# ProProject_MinSyBo_Star_2024-05-27.net
KiCad netlist of a schematic drawn in EasyEDA Pro
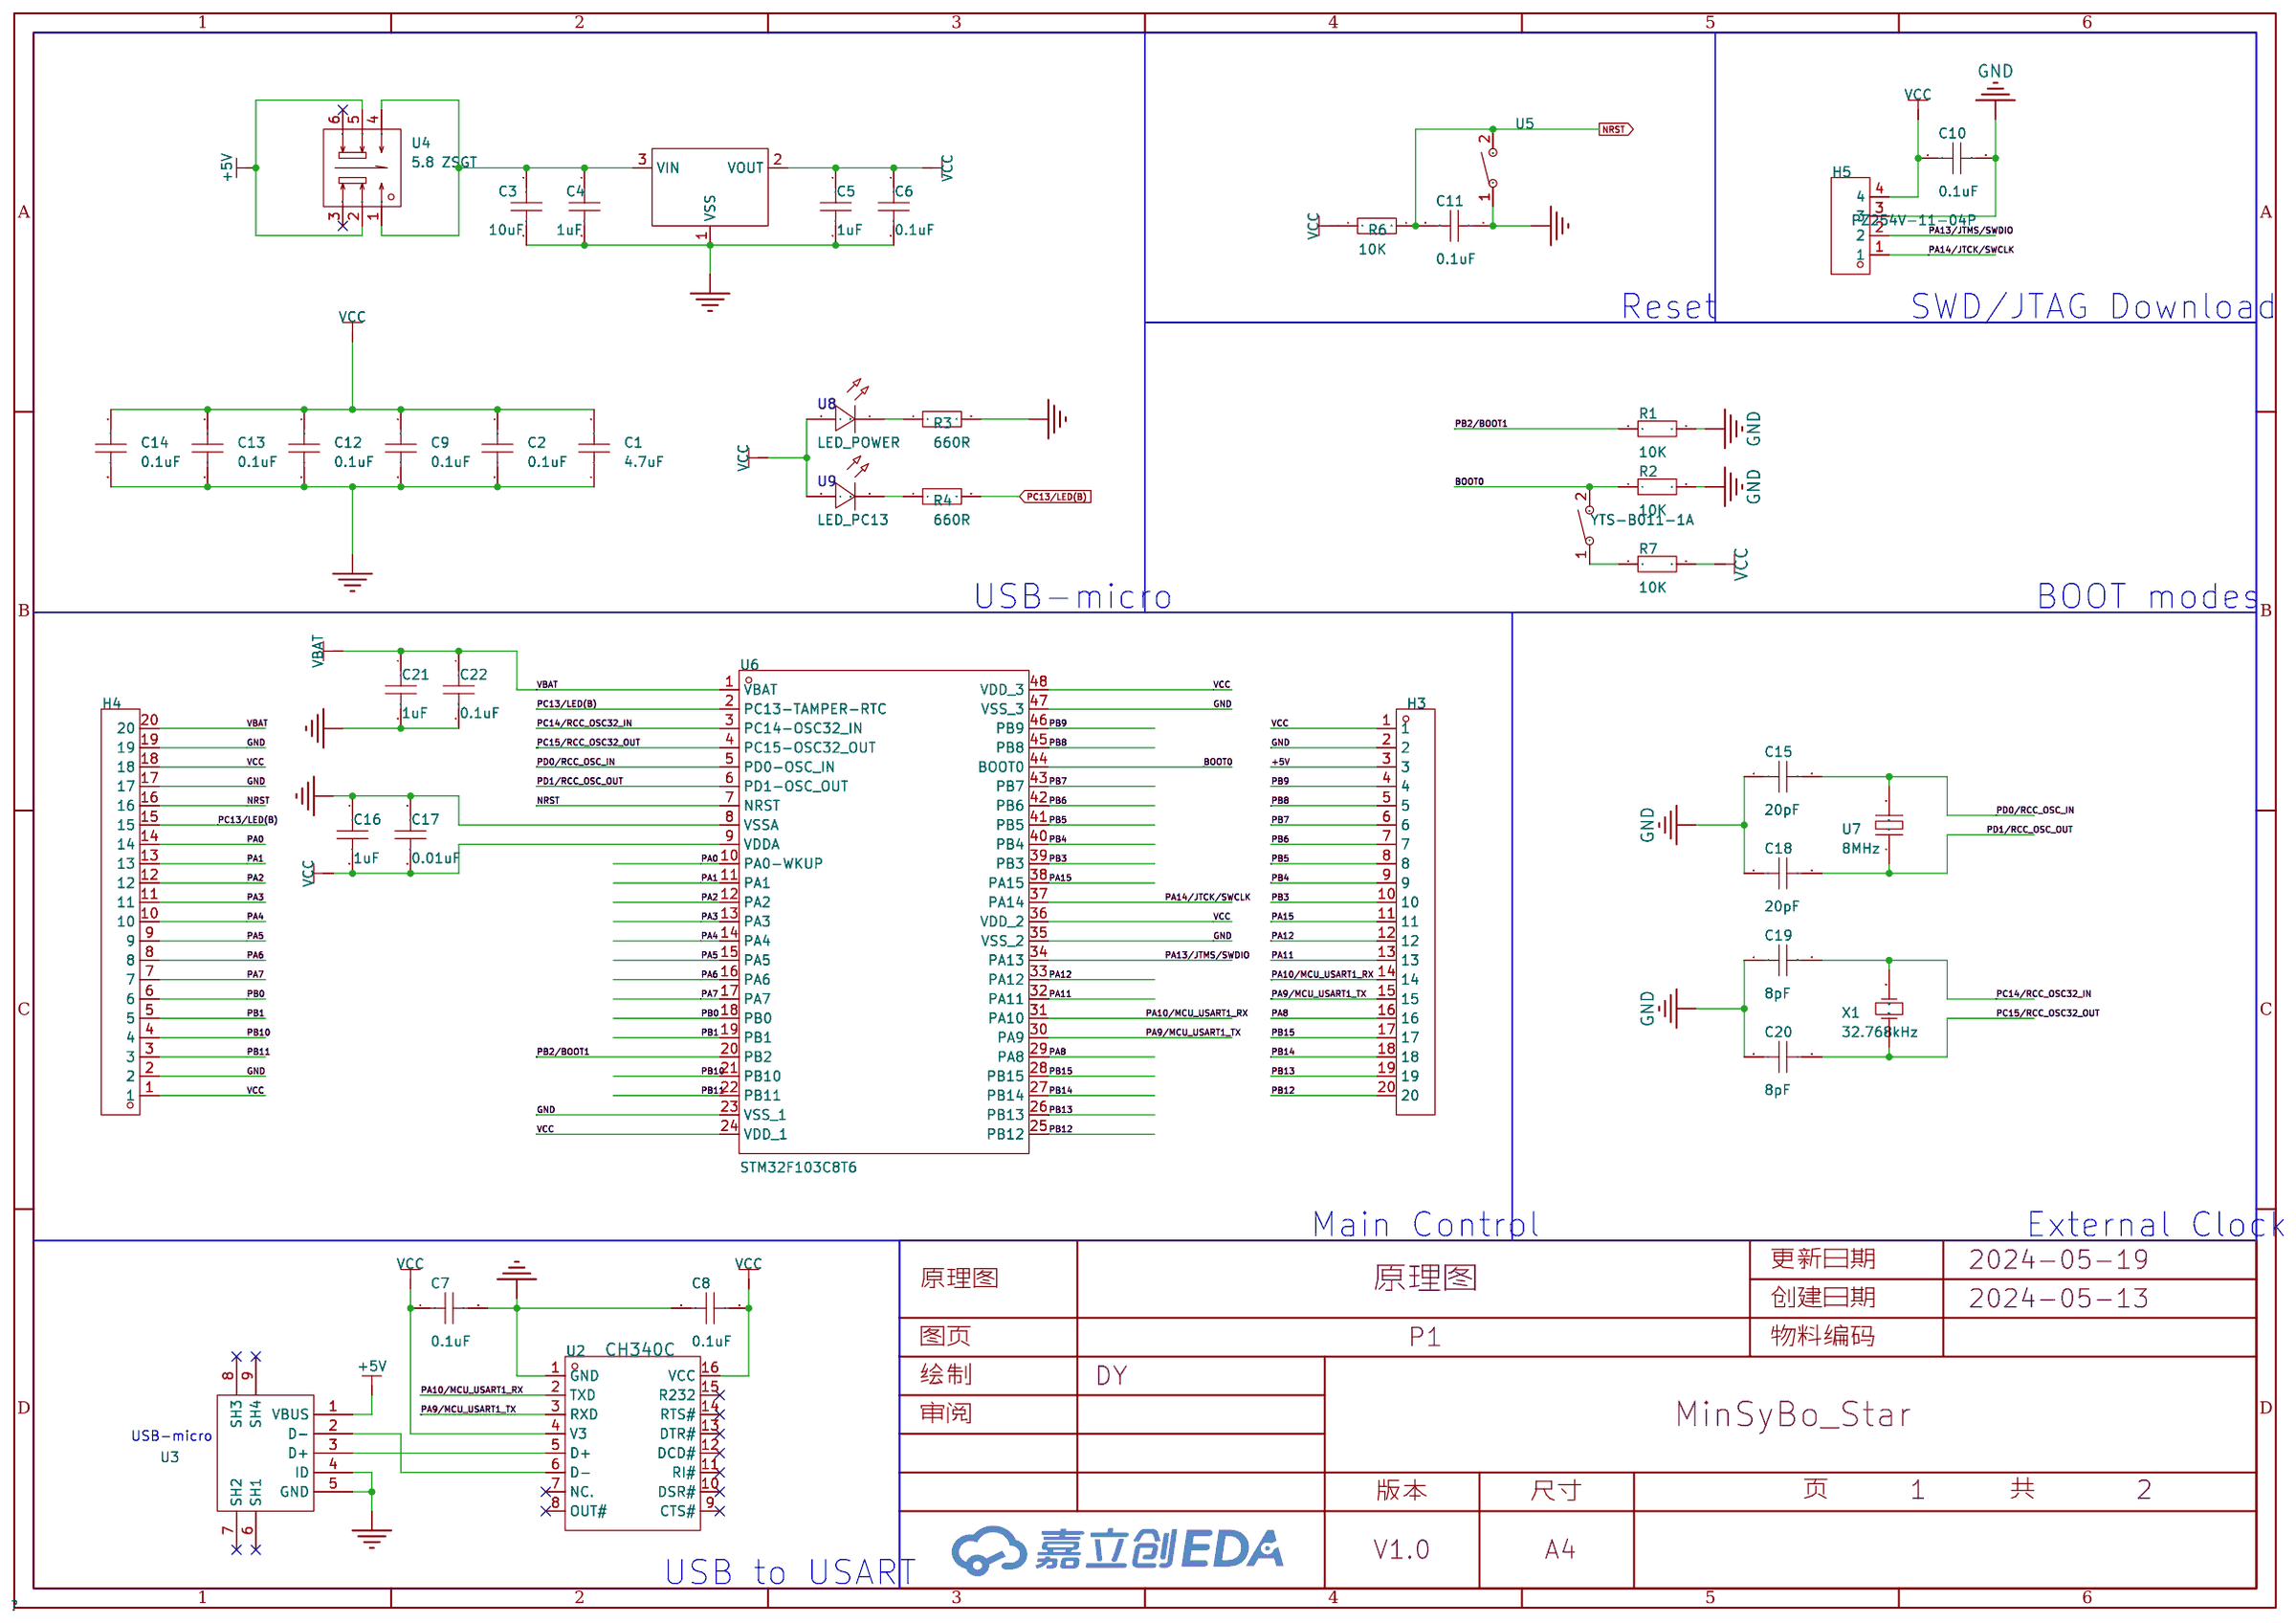
[diagram p0: P1]
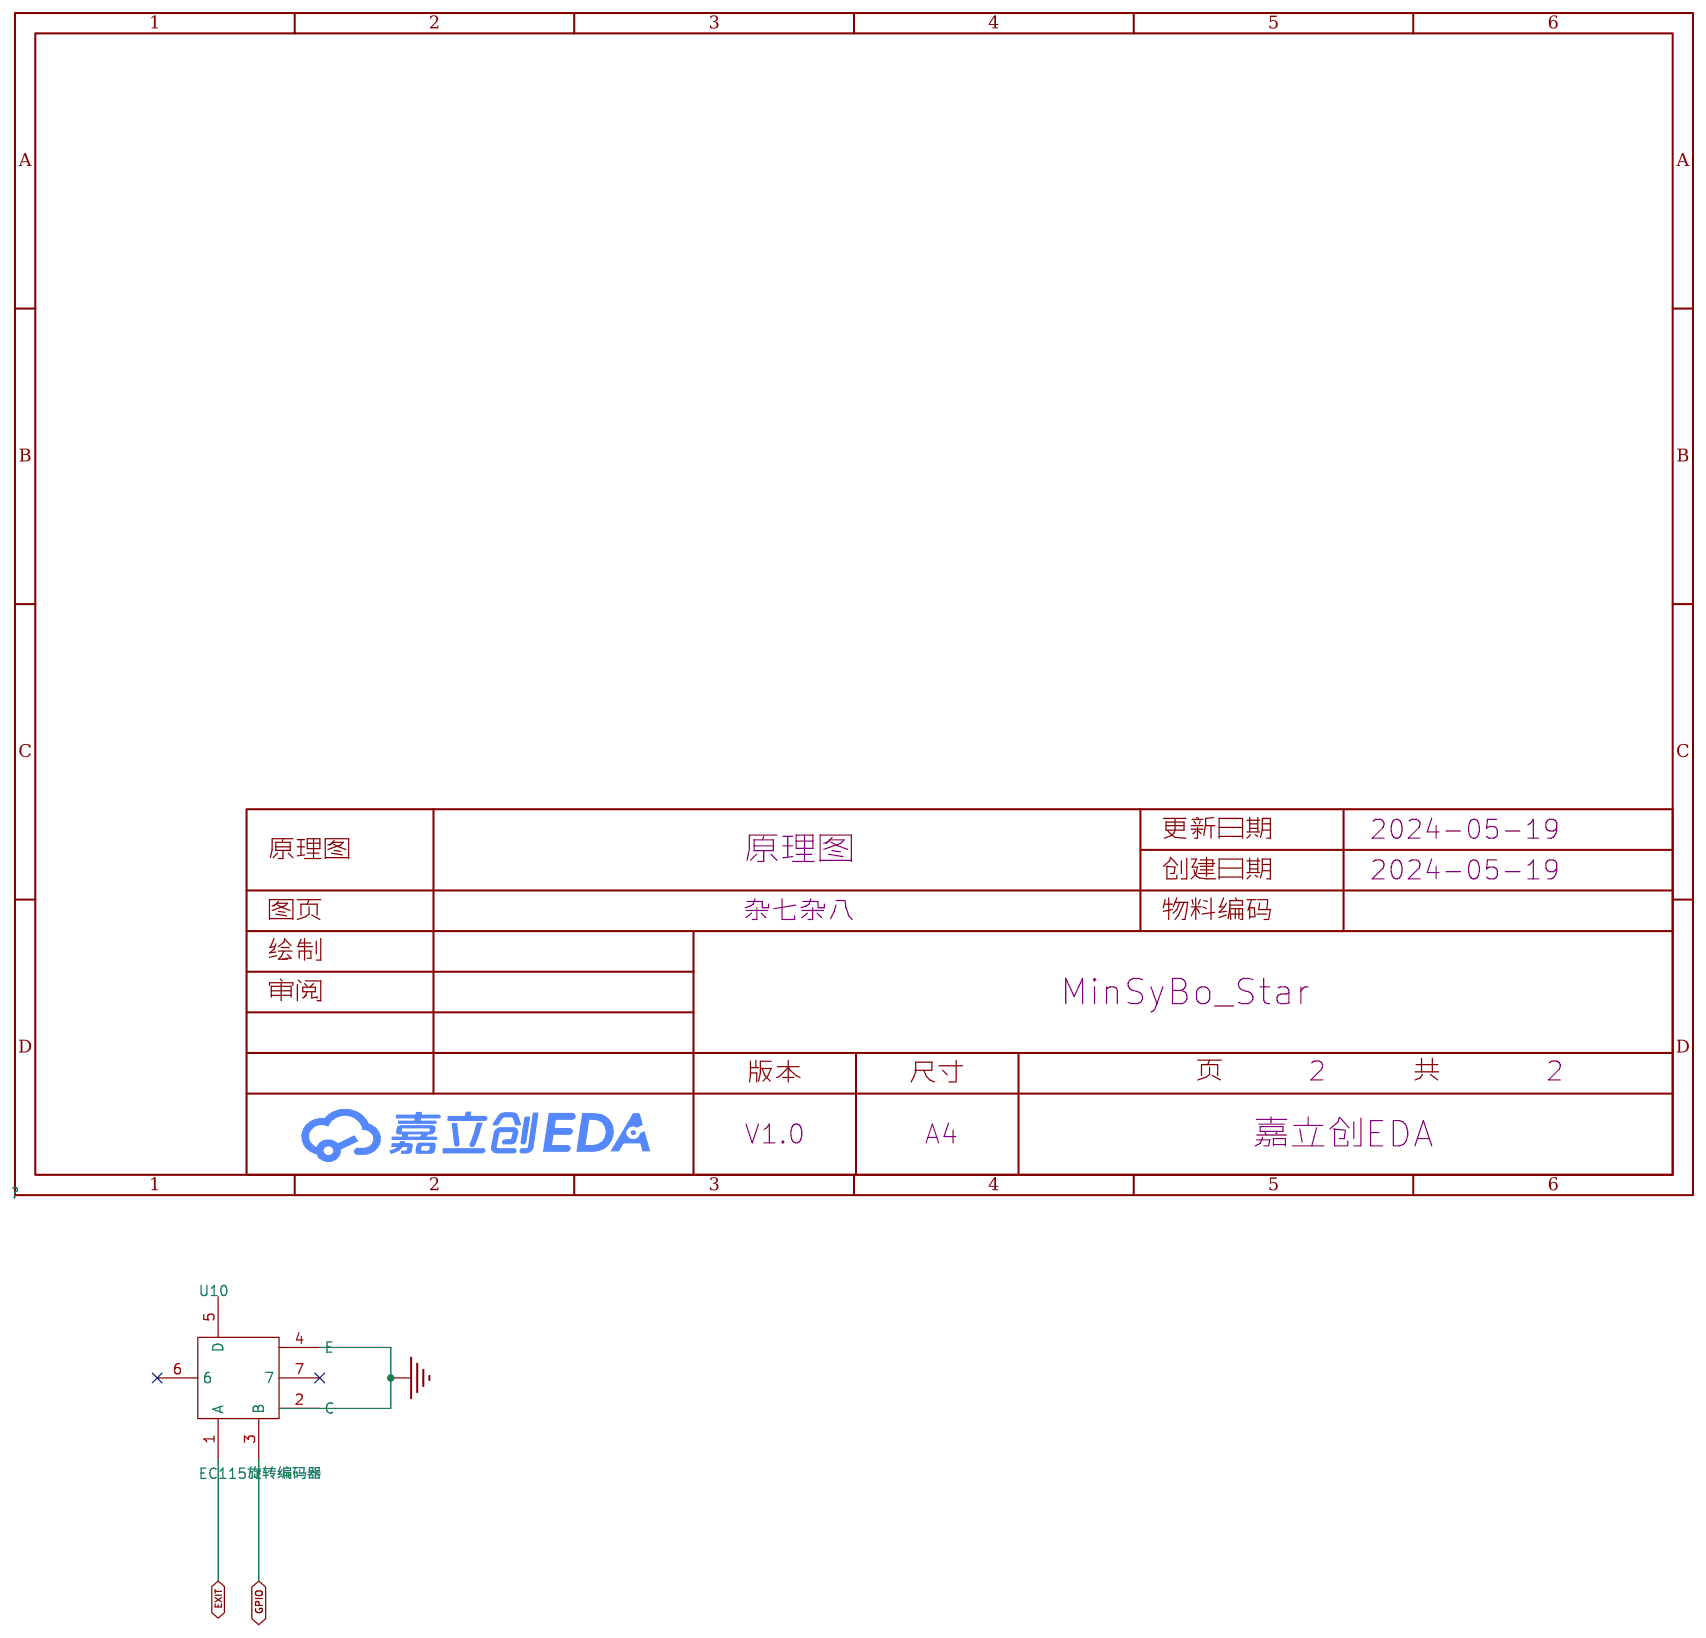
[diagram p1: 杂七杂八]

(export (version "E")
  (design (tool "Eeschema 10.0.6"))
  (components
    (comp (ref "BOOT0")
      (value "YTS-B011-1A")
      (footprint "easyedapro:SW-TH_L6.1-W3.5-P6.60-LS8.0")
      (fields (field (name "Manufacturer") "YIYUAN(怡远)"))
      (libsource (lib "easyedapro") (part "YTS-B011-1A"))
    )
    (comp (ref "C1")
      (value "4.7uF")
      (footprint "easyedapro:C0603")
      (libsource (lib "easyedapro") (part "CapAcitance"))
    )
    (comp (ref "C2")
      (value "100nF")
      (footprint "easyedapro:C0603")
      (libsource (lib "easyedapro") (part "CapAcitance"))
    )
    (comp (ref "C3")
      (value "10uF")
      (footprint "easyedapro:C0603")
      (fields
        (field (name "Manufacturer Part") "CL10A106KP8NNNC")
        (field (name "Manufacturer") "SAMSUNG(三星)")
        (field (name "Tolerance") "±10%")
      )
      (libsource (lib "easyedapro") (part "CapAcitance"))
    )
    (comp (ref "C4")
      (value "1uF")
      (footprint "easyedapro:C0603")
      (libsource (lib "easyedapro") (part "CapAcitance"))
    )
    (comp (ref "C5")
      (value "1uF")
      (footprint "easyedapro:C0603")
      (libsource (lib "easyedapro") (part "CapAcitance"))
    )
    (comp (ref "C6")
      (value "0.1uF")
      (footprint "easyedapro:C0603")
      (libsource (lib "easyedapro") (part "CapAcitance"))
    )
    (comp (ref "C7")
      (value "0.1uF")
      (footprint "easyedapro:C0603")
      (libsource (lib "easyedapro") (part "CapAcitance"))
    )
    (comp (ref "C8")
      (value "0.1uF")
      (footprint "easyedapro:C0603")
      (libsource (lib "easyedapro") (part "CapAcitance"))
    )
    (comp (ref "C9")
      (value "100nF")
      (footprint "easyedapro:C0603")
      (libsource (lib "easyedapro") (part "CapAcitance"))
    )
    (comp (ref "C10")
      (value "0.1uF")
      (footprint "easyedapro:C0603")
      (libsource (lib "easyedapro") (part "CapAcitance"))
    )
    (comp (ref "C11")
      (value "0.1uF")
      (footprint "easyedapro:C0603")
      (libsource (lib "easyedapro") (part "CapAcitance"))
    )
    (comp (ref "C12")
      (value "100nF")
      (footprint "easyedapro:C0603")
      (libsource (lib "easyedapro") (part "CapAcitance"))
    )
    (comp (ref "C13")
      (value "100nF")
      (footprint "easyedapro:C0603")
      (libsource (lib "easyedapro") (part "CapAcitance"))
    )
    (comp (ref "C14")
      (value "100nF")
      (footprint "easyedapro:C0603")
      (libsource (lib "easyedapro") (part "CapAcitance"))
    )
    (comp (ref "C15")
      (value "20pF")
      (footprint "easyedapro:C0603")
      (libsource (lib "easyedapro") (part "CapAcitance"))
    )
    (comp (ref "C16")
      (value "1uF")
      (footprint "easyedapro:C0603")
      (libsource (lib "easyedapro") (part "CapAcitance"))
    )
    (comp (ref "C17")
      (value "0.01uF")
      (footprint "easyedapro:C0603")
      (libsource (lib "easyedapro") (part "CapAcitance"))
    )
    (comp (ref "C18")
      (value "20pF")
      (footprint "easyedapro:C0603")
      (libsource (lib "easyedapro") (part "CapAcitance"))
    )
    (comp (ref "C19")
      (value "8pF")
      (footprint "easyedapro:C0603")
      (libsource (lib "easyedapro") (part "CapAcitance"))
    )
    (comp (ref "C20")
      (value "8pF")
      (footprint "easyedapro:C0603")
      (libsource (lib "easyedapro") (part "CapAcitance"))
    )
    (comp (ref "C21")
      (value "1uF")
      (footprint "easyedapro:C0603")
      (libsource (lib "easyedapro") (part "CapAcitance"))
    )
    (comp (ref "C22")
      (value "0.1uF")
      (footprint "easyedapro:C0603")
      (libsource (lib "easyedapro") (part "CapAcitance"))
    )
    (comp (ref "H3")
      (value "2.54-1*20P直针")
      (footprint "easyedapro:HDR-TH_20P-P2.54-V-M-1")
      (fields (field (name "Manufacturer") "BOOMELE(博穆精密)"))
      (libsource (lib "easyedapro") (part "HDR_2.54-1x20P"))
    )
    (comp (ref "H4")
      (value "2.54-1*20P直针")
      (footprint "easyedapro:HDR-TH_20P-P2.54-V-M-1")
      (fields (field (name "Manufacturer") "BOOMELE(博穆精密)"))
      (libsource (lib "easyedapro") (part "HDR_2.54-1x20P"))
    )
    (comp (ref "H5")
      (value "PZ254V-11-04P")
      (footprint "easyedapro:HDR-TH_4P-P2.54-V-M")
      (fields (field (name "Manufacturer") "XFCN(兴飞)"))
      (libsource (lib "easyedapro") (part "PZ254V-11-04P"))
    )
    (comp (ref "R1") (value "10K") (footprint "easyedapro:R0603") (libsource (lib "easyedapro") (part "电阻")))
    (comp (ref "R2") (value "10K") (footprint "easyedapro:R0603") (libsource (lib "easyedapro") (part "电阻")))
    (comp (ref "R3") (value "660R") (footprint "easyedapro:R0603") (libsource (lib "easyedapro") (part "电阻")))
    (comp (ref "R4") (value "660R") (footprint "easyedapro:R0603") (libsource (lib "easyedapro") (part "电阻")))
    (comp (ref "R6") (value "10K") (footprint "easyedapro:R0603") (libsource (lib "easyedapro") (part "电阻")))
    (comp (ref "R7") (value "10K") (footprint "easyedapro:R0603") (libsource (lib "easyedapro") (part "电阻")))
    (comp (ref "U1")
      (value "XC6206P332MR")
      (footprint "easyedapro:SOT-23-3_L2.9-W1.3-P1.90-LS2.4-BR")
      (description "输出类型:固定;最大输入电压:8V;输出电压:3.3V;最大输出电流:300mA;输出极性:正极;")
      (fields (field (name "Manufacturer") "HXY MOSFET(华轩阳电子)"))
      (libsource (lib "easyedapro") (part "XC6206P332MR_C5148692"))
    )
    (comp (ref "U2")
      (value "CH340C")
      (footprint "easyedapro:SOP-16_L10.0-W3.9-P1.27-LS6.0-BL")
      (description "应用功能:收发器;接口协议:USB 2.0;数据速率:2Mbps;")
      (fields (field (name "Manufacturer") "WCH(南京沁恒)"))
      (libsource (lib "easyedapro") (part "CH340C"))
    )
    (comp (ref "U3")
      (value "MicroXNJ")
      (footprint "easyedapro:MICRO-USB-SMD_MICROXNJ")
      (description "连接器类型:Micro-B;标准:USB 2.0;公母:母;端口数量:1;触点数量:5P;安装方式:卧贴;额定电流 - 电源:1A;工作温度范围:-20°C~+85°C;")
      (fields (field (name "Manufacturer") "SHOU HAN(首韩)"))
      (libsource (lib "easyedapro") (part "MICROXNJ"))
    )
    (comp (ref "U4")
      (value "5.8 ZSGT")
      (footprint "easyedapro:SW-TH_5.8ZSGT")
      (description "电路结构:双刀双掷;自锁/无锁:自锁;安装方式:直插;触点电流:110mA;额定电压 (DC):30V;带灯:不带;作用力:150gf;机械寿命:10万次;")
      (fields (field (name "Manufacturer") "SHOU HAN(首韩)"))
      (libsource (lib "easyedapro") (part "5.8 ZSGT"))
    )
    (comp (ref "U5")
      (value "YTS-B011-1A")
      (footprint "easyedapro:SW-TH_L6.1-W3.5-P6.60-LS8.0")
      (fields (field (name "Manufacturer") "YIYUAN(怡远)"))
      (libsource (lib "easyedapro") (part "YTS-B011-1A"))
    )
    (comp (ref "U6")
      (value "STM32F103C8T6")
      (footprint "easyedapro:LQFP-48_L7.0-W7.0-P0.50-LS9.0-BL")
      (description "CPU内核:ARM-M3;程序存储容量:64KB;RAM总容量:20KB;GPIO端口数量:37;工作电压范围:2V~3.6V;CPU最大主频:72MHz;程序存储器类型:FLASH;")
      (fields (field (name "Manufacturer") "ST(意法半导体)"))
      (libsource (lib "easyedapro") (part "STM32F103C8T6"))
    )
    (comp (ref "U7")
      (value "8MHz")
      (footprint "easyedapro:HC-49SMD_L11.1-W4.8")
      (description "晶振类型:贴片晶振;频率:8MHz;常温频差:±10ppm;外接负载电容:20pF;频率稳定度(全温):±30ppm;")
      (fields (field (name "Manufacturer Part") "RC08000619") (field (name "Manufacturer") "TROQ(创捷)"))
      (libsource (lib "easyedapro") (part "RC08000619"))
    )
    (comp (ref "U8")
      (value "LED_POWER")
      (footprint "easyedapro:LED_0603")
      (libsource (lib "easyedapro") (part "LED_G"))
    )
    (comp (ref "U9")
      (value "LED_PC13")
      (footprint "easyedapro:LED_0603")
      (libsource (lib "easyedapro") (part "LED_B"))
    )
    (comp (ref "X1")
      (value "32.768kHz")
      (footprint "easyedapro:OSC-TH_BD3.8-P0.50")
      (description "晶振类型:直插晶振;频率:32.768kHz;常温频差:±20ppm;外接负载电容:12.5pF;频率稳定度(全温):±20ppm;")
      (fields (field (name "Manufacturer Part") "K383276812520") (field (name "Manufacturer") "KYX(凯越翔)"))
      (libsource (lib "easyedapro") (part "K383276812520"))
    )
    (comp (ref "U10")
      (value "EC115旋转编码器")
      (footprint "easyedapro:SW-SMD_EC115_C9900036245")
      (libsource (lib "easyedapro") (part "EC115旋转编码器"))
    )
  )
  (nets
    (net (code "1") (name "+5V") (class "Default")
      (node (ref "H3") (pin "3") (pinfunction "3_3") (pintype "input"))
      (node (ref "U3") (pin "1") (pinfunction "VBUS_1") (pintype "unspecified"))
      (node (ref "U4") (pin "2") (pinfunction "2_2") (pintype "unspecified"))
      (node (ref "U4") (pin "5") (pinfunction "5_5") (pintype "unspecified"))
    )
    (net (code "2") (name "BOOT0") (class "Default")
      (node (ref "BOOT0") (pin "2") (pinfunction "2_2") (pintype "unspecified"))
      (node (ref "R2") (pin "1") (pinfunction "1_1") (pintype "input"))
      (node (ref "U6") (pin "44") (pinfunction "BOOT0_44") (pintype "unspecified"))
    )
    (net (code "3") (name "EXIT") (class "Default")
      (node (ref "U10") (pin "1") (pinfunction "A_1") (pintype "unspecified"))
    )
    (net (code "4") (name "GND") (class "Default")
      (node (ref "C1") (pin "1") (pinfunction "1_1") (pintype "input"))
      (node (ref "C10") (pin "2") (pinfunction "2_2") (pintype "input"))
      (node (ref "C11") (pin "1") (pinfunction "1_1") (pintype "input"))
      (node (ref "C12") (pin "2") (pinfunction "2_2") (pintype "input"))
      (node (ref "C13") (pin "2") (pinfunction "2_2") (pintype "input"))
      (node (ref "C14") (pin "2") (pinfunction "2_2") (pintype "input"))
      (node (ref "C15") (pin "1") (pinfunction "1_1") (pintype "input"))
      (node (ref "C16") (pin "1") (pinfunction "1_1") (pintype "input"))
      (node (ref "C17") (pin "1") (pinfunction "1_1") (pintype "input"))
      (node (ref "C18") (pin "1") (pinfunction "1_1") (pintype "input"))
      (node (ref "C19") (pin "1") (pinfunction "1_1") (pintype "input"))
      (node (ref "C2") (pin "2") (pinfunction "2_2") (pintype "input"))
      (node (ref "C20") (pin "1") (pinfunction "1_1") (pintype "input"))
      (node (ref "C21") (pin "2") (pinfunction "2_2") (pintype "input"))
      (node (ref "C22") (pin "2") (pinfunction "2_2") (pintype "input"))
      (node (ref "C3") (pin "2") (pinfunction "2_2") (pintype "input"))
      (node (ref "C4") (pin "2") (pinfunction "2_2") (pintype "input"))
      (node (ref "C5") (pin "2") (pinfunction "2_2") (pintype "input"))
      (node (ref "C6") (pin "2") (pinfunction "2_2") (pintype "input"))
      (node (ref "C7") (pin "2") (pinfunction "2_2") (pintype "input"))
      (node (ref "C8") (pin "1") (pinfunction "1_1") (pintype "input"))
      (node (ref "C9") (pin "2") (pinfunction "2_2") (pintype "input"))
      (node (ref "H3") (pin "2") (pinfunction "2_2") (pintype "input"))
      (node (ref "H4") (pin "17") (pinfunction "17_17") (pintype "input"))
      (node (ref "H4") (pin "19") (pinfunction "19_19") (pintype "input"))
      (node (ref "H4") (pin "2") (pinfunction "2_2") (pintype "input"))
      (node (ref "H5") (pin "3") (pinfunction "3_3") (pintype "unspecified"))
      (node (ref "R1") (pin "1") (pinfunction "1_1") (pintype "input"))
      (node (ref "R2") (pin "2") (pinfunction "2_2") (pintype "input"))
      (node (ref "R3") (pin "2") (pinfunction "2_2") (pintype "input"))
      (node (ref "U1") (pin "1") (pinfunction "VSS_1") (pintype "unspecified"))
      (node (ref "U10") (pin "2") (pinfunction "C_2") (pintype "unspecified"))
      (node (ref "U2") (pin "1") (pinfunction "GND_1") (pintype "unspecified"))
      (node (ref "U3") (pin "4") (pinfunction "ID_4") (pintype "unspecified"))
      (node (ref "U3") (pin "5") (pinfunction "GND_5") (pintype "unspecified"))
      (node (ref "U5") (pin "1") (pinfunction "1_1") (pintype "unspecified"))
      (node (ref "U6") (pin "23") (pinfunction "VSS_1_23") (pintype "unspecified"))
      (node (ref "U6") (pin "35") (pinfunction "VSS_2_35") (pintype "unspecified"))
      (node (ref "U6") (pin "47") (pinfunction "VSS_3_47") (pintype "unspecified"))
      (node (ref "U6") (pin "8") (pinfunction "VSSA_8") (pintype "unspecified"))
    )
    (net (code "5") (name "GPIO") (class "Default")
      (node (ref "U10") (pin "3") (pinfunction "B_3") (pintype "unspecified"))
    )
    (net (code "6") (name "NRST") (class "Default")
      (node (ref "C11") (pin "2") (pinfunction "2_2") (pintype "input"))
      (node (ref "H4") (pin "16") (pinfunction "16_16") (pintype "input"))
      (node (ref "R6") (pin "2") (pinfunction "2_2") (pintype "input"))
      (node (ref "U5") (pin "2") (pinfunction "2_2") (pintype "unspecified"))
      (node (ref "U6") (pin "7") (pinfunction "NRST_7") (pintype "unspecified"))
    )
    (net (code "7") (name "Net-(BOOT0-Pad1)") (class "Default")
      (node (ref "BOOT0") (pin "1") (pinfunction "1_1") (pintype "unspecified"))
      (node (ref "R7") (pin "1") (pinfunction "1_1") (pintype "input"))
    )
    (net (code "8") (name "Net-(U1-VIN)") (class "Default")
      (node (ref "C3") (pin "1") (pinfunction "1_1") (pintype "input"))
      (node (ref "C4") (pin "1") (pinfunction "1_1") (pintype "input"))
      (node (ref "U1") (pin "3") (pinfunction "VIN_3") (pintype "unspecified"))
      (node (ref "U4") (pin "1") (pinfunction "1_1") (pintype "unspecified"))
      (node (ref "U4") (pin "4") (pinfunction "4_4") (pintype "unspecified"))
    )
    (net (code "9") (name "Net-(U2-D+)") (class "Default")
      (node (ref "U2") (pin "5") (pinfunction "D+_5") (pintype "unspecified"))
      (node (ref "U3") (pin "3") (pinfunction "D+_3") (pintype "unspecified"))
    )
    (net (code "10") (name "Net-(U2-D-)") (class "Default")
      (node (ref "U2") (pin "6") (pinfunction "D-_6") (pintype "unspecified"))
      (node (ref "U3") (pin "2") (pinfunction "D-_2") (pintype "unspecified"))
    )
    (net (code "11") (name "Net-(U8-C)") (class "Default")
      (node (ref "R3") (pin "1") (pinfunction "1_1") (pintype "input"))
      (node (ref "U8") (pin "1") (pinfunction "C_1") (pintype "input"))
    )
    (net (code "12") (name "Net-(U9-C)") (class "Default")
      (node (ref "R4") (pin "1") (pinfunction "1_1") (pintype "input"))
      (node (ref "U9") (pin "1") (pinfunction "C_1") (pintype "input"))
    )
    (net (code "13") (name "PA0") (class "Default")
      (node (ref "H4") (pin "14") (pinfunction "14_14") (pintype "input"))
      (node (ref "U6") (pin "10") (pinfunction "PA0-WKUP_10") (pintype "unspecified"))
    )
    (net (code "14") (name "PA1") (class "Default")
      (node (ref "H4") (pin "13") (pinfunction "13_13") (pintype "input"))
      (node (ref "U6") (pin "11") (pinfunction "PA1_11") (pintype "unspecified"))
    )
    (net (code "15") (name "PA2") (class "Default")
      (node (ref "H4") (pin "12") (pinfunction "12_12") (pintype "input"))
      (node (ref "U6") (pin "12") (pinfunction "PA2_12") (pintype "unspecified"))
    )
    (net (code "16") (name "PA3") (class "Default")
      (node (ref "H4") (pin "11") (pinfunction "11_11") (pintype "input"))
      (node (ref "U6") (pin "13") (pinfunction "PA3_13") (pintype "unspecified"))
    )
    (net (code "17") (name "PA4") (class "Default")
      (node (ref "H4") (pin "10") (pinfunction "10_10") (pintype "input"))
      (node (ref "U6") (pin "14") (pinfunction "PA4_14") (pintype "unspecified"))
    )
    (net (code "18") (name "PA5") (class "Default")
      (node (ref "H4") (pin "9") (pinfunction "9_9") (pintype "input"))
      (node (ref "U6") (pin "15") (pinfunction "PA5_15") (pintype "unspecified"))
    )
    (net (code "19") (name "PA6") (class "Default")
      (node (ref "H4") (pin "8") (pinfunction "8_8") (pintype "input"))
      (node (ref "U6") (pin "16") (pinfunction "PA6_16") (pintype "unspecified"))
    )
    (net (code "20") (name "PA7") (class "Default")
      (node (ref "H4") (pin "7") (pinfunction "7_7") (pintype "input"))
      (node (ref "U6") (pin "17") (pinfunction "PA7_17") (pintype "unspecified"))
    )
    (net (code "21") (name "PA8") (class "Default")
      (node (ref "H3") (pin "16") (pinfunction "16_16") (pintype "input"))
      (node (ref "U6") (pin "29") (pinfunction "PA8_29") (pintype "unspecified"))
    )
    (net (code "22") (name "PA9{slash}MCU_USART1_TX") (class "Default")
      (node (ref "H3") (pin "15") (pinfunction "15_15") (pintype "input"))
      (node (ref "U2") (pin "3") (pinfunction "RXD_3") (pintype "unspecified"))
      (node (ref "U6") (pin "30") (pinfunction "PA9_30") (pintype "unspecified"))
    )
    (net (code "23") (name "PA10{slash}MCU_USART1_RX") (class "Default")
      (node (ref "H3") (pin "14") (pinfunction "14_14") (pintype "input"))
      (node (ref "U2") (pin "2") (pinfunction "TXD_2") (pintype "unspecified"))
      (node (ref "U6") (pin "31") (pinfunction "PA10_31") (pintype "unspecified"))
    )
    (net (code "24") (name "PA11") (class "Default")
      (node (ref "H3") (pin "13") (pinfunction "13_13") (pintype "input"))
      (node (ref "U6") (pin "32") (pinfunction "PA11_32") (pintype "unspecified"))
    )
    (net (code "25") (name "PA12") (class "Default")
      (node (ref "H3") (pin "12") (pinfunction "12_12") (pintype "input"))
      (node (ref "U6") (pin "33") (pinfunction "PA12_33") (pintype "unspecified"))
    )
    (net (code "26") (name "PA13{slash}JTMS{slash}SWDIO") (class "Default")
      (node (ref "H5") (pin "2") (pinfunction "2_2") (pintype "unspecified"))
      (node (ref "U6") (pin "34") (pinfunction "PA13_34") (pintype "unspecified"))
    )
    (net (code "27") (name "PA14{slash}JTCK{slash}SWCLK") (class "Default")
      (node (ref "H5") (pin "1") (pinfunction "1_1") (pintype "unspecified"))
      (node (ref "U6") (pin "37") (pinfunction "PA14_37") (pintype "unspecified"))
    )
    (net (code "28") (name "PA15") (class "Default")
      (node (ref "H3") (pin "11") (pinfunction "11_11") (pintype "input"))
      (node (ref "U6") (pin "38") (pinfunction "PA15_38") (pintype "unspecified"))
    )
    (net (code "29") (name "PB0") (class "Default")
      (node (ref "H4") (pin "6") (pinfunction "6_6") (pintype "input"))
      (node (ref "U6") (pin "18") (pinfunction "PB0_18") (pintype "unspecified"))
    )
    (net (code "30") (name "PB1") (class "Default")
      (node (ref "H4") (pin "5") (pinfunction "5_5") (pintype "input"))
      (node (ref "U6") (pin "19") (pinfunction "PB1_19") (pintype "unspecified"))
    )
    (net (code "31") (name "PB2{slash}BOOT1") (class "Default")
      (node (ref "R1") (pin "2") (pinfunction "2_2") (pintype "input"))
      (node (ref "U6") (pin "20") (pinfunction "PB2_20") (pintype "unspecified"))
    )
    (net (code "32") (name "PB3") (class "Default")
      (node (ref "H3") (pin "10") (pinfunction "10_10") (pintype "input"))
      (node (ref "U6") (pin "39") (pinfunction "PB3_39") (pintype "unspecified"))
    )
    (net (code "33") (name "PB4") (class "Default")
      (node (ref "H3") (pin "9") (pinfunction "9_9") (pintype "input"))
      (node (ref "U6") (pin "40") (pinfunction "PB4_40") (pintype "unspecified"))
    )
    (net (code "34") (name "PB5") (class "Default")
      (node (ref "H3") (pin "8") (pinfunction "8_8") (pintype "input"))
      (node (ref "U6") (pin "41") (pinfunction "PB5_41") (pintype "unspecified"))
    )
    (net (code "35") (name "PB6") (class "Default")
      (node (ref "H3") (pin "7") (pinfunction "7_7") (pintype "input"))
      (node (ref "U6") (pin "42") (pinfunction "PB6_42") (pintype "unspecified"))
    )
    (net (code "36") (name "PB7") (class "Default")
      (node (ref "H3") (pin "6") (pinfunction "6_6") (pintype "input"))
      (node (ref "U6") (pin "43") (pinfunction "PB7_43") (pintype "unspecified"))
    )
    (net (code "37") (name "PB8") (class "Default")
      (node (ref "H3") (pin "5") (pinfunction "5_5") (pintype "input"))
      (node (ref "U6") (pin "45") (pinfunction "PB8_45") (pintype "unspecified"))
    )
    (net (code "38") (name "PB9") (class "Default")
      (node (ref "H3") (pin "4") (pinfunction "4_4") (pintype "input"))
      (node (ref "U6") (pin "46") (pinfunction "PB9_46") (pintype "unspecified"))
    )
    (net (code "39") (name "PB10") (class "Default")
      (node (ref "H4") (pin "4") (pinfunction "4_4") (pintype "input"))
      (node (ref "U6") (pin "21") (pinfunction "PB10_21") (pintype "unspecified"))
    )
    (net (code "40") (name "PB11") (class "Default")
      (node (ref "H4") (pin "3") (pinfunction "3_3") (pintype "input"))
      (node (ref "U6") (pin "22") (pinfunction "PB11_22") (pintype "unspecified"))
    )
    (net (code "41") (name "PB12") (class "Default")
      (node (ref "H3") (pin "20") (pinfunction "20_20") (pintype "input"))
      (node (ref "U6") (pin "25") (pinfunction "PB12_25") (pintype "unspecified"))
    )
    (net (code "42") (name "PB13") (class "Default")
      (node (ref "H3") (pin "19") (pinfunction "19_19") (pintype "input"))
      (node (ref "U6") (pin "26") (pinfunction "PB13_26") (pintype "unspecified"))
    )
    (net (code "43") (name "PB14") (class "Default")
      (node (ref "H3") (pin "18") (pinfunction "18_18") (pintype "input"))
      (node (ref "U6") (pin "27") (pinfunction "PB14_27") (pintype "unspecified"))
    )
    (net (code "44") (name "PB15") (class "Default")
      (node (ref "H3") (pin "17") (pinfunction "17_17") (pintype "input"))
      (node (ref "U6") (pin "28") (pinfunction "PB15_28") (pintype "unspecified"))
    )
    (net (code "45") (name "PC13{slash}LED(B)") (class "Default")
      (node (ref "H4") (pin "15") (pinfunction "15_15") (pintype "input"))
      (node (ref "R4") (pin "2") (pinfunction "2_2") (pintype "input"))
      (node (ref "U6") (pin "2") (pinfunction "PC13-TAMPER-RTC_2") (pintype "unspecified"))
    )
    (net (code "46") (name "PC14{slash}RCC_OSC32_IN") (class "Default")
      (node (ref "C19") (pin "2") (pinfunction "2_2") (pintype "input"))
      (node (ref "U6") (pin "3") (pinfunction "PC14-OSC32_IN_3") (pintype "unspecified"))
      (node (ref "X1") (pin "2") (pinfunction "OSC2_2") (pintype "unspecified"))
    )
    (net (code "47") (name "PC15{slash}RCC_OSC32_OUT") (class "Default")
      (node (ref "C20") (pin "2") (pinfunction "2_2") (pintype "input"))
      (node (ref "U6") (pin "4") (pinfunction "PC15-OSC32_OUT_4") (pintype "unspecified"))
      (node (ref "X1") (pin "1") (pinfunction "OSC1_1") (pintype "unspecified"))
    )
    (net (code "48") (name "PD0{slash}RCC_OSC_IN") (class "Default")
      (node (ref "C15") (pin "2") (pinfunction "2_2") (pintype "input"))
      (node (ref "U6") (pin "5") (pinfunction "PD0-OSC_IN_5") (pintype "unspecified"))
      (node (ref "U7") (pin "2") (pinfunction "GND_2") (pintype "input"))
    )
    (net (code "49") (name "PD1{slash}RCC_OSC_OUT") (class "Default")
      (node (ref "C18") (pin "2") (pinfunction "2_2") (pintype "input"))
      (node (ref "U6") (pin "6") (pinfunction "PD1-OSC_OUT_6") (pintype "unspecified"))
      (node (ref "U7") (pin "1") (pinfunction "1_1") (pintype "input"))
    )
    (net (code "50") (name "VBAT") (class "Default")
      (node (ref "C21") (pin "1") (pinfunction "1_1") (pintype "input"))
      (node (ref "C22") (pin "1") (pinfunction "1_1") (pintype "input"))
      (node (ref "H4") (pin "20") (pinfunction "20_20") (pintype "input"))
      (node (ref "U6") (pin "1") (pinfunction "VBAT_1") (pintype "unspecified"))
    )
    (net (code "51") (name "VCC") (class "Default")
      (node (ref "C1") (pin "2") (pinfunction "2_2") (pintype "input"))
      (node (ref "C10") (pin "1") (pinfunction "1_1") (pintype "input"))
      (node (ref "C12") (pin "1") (pinfunction "1_1") (pintype "input"))
      (node (ref "C13") (pin "1") (pinfunction "1_1") (pintype "input"))
      (node (ref "C14") (pin "1") (pinfunction "1_1") (pintype "input"))
      (node (ref "C16") (pin "2") (pinfunction "2_2") (pintype "input"))
      (node (ref "C17") (pin "2") (pinfunction "2_2") (pintype "input"))
      (node (ref "C2") (pin "1") (pinfunction "1_1") (pintype "input"))
      (node (ref "C5") (pin "1") (pinfunction "1_1") (pintype "input"))
      (node (ref "C6") (pin "1") (pinfunction "1_1") (pintype "input"))
      (node (ref "C7") (pin "1") (pinfunction "1_1") (pintype "input"))
      (node (ref "C8") (pin "2") (pinfunction "2_2") (pintype "input"))
      (node (ref "C9") (pin "1") (pinfunction "1_1") (pintype "input"))
      (node (ref "H3") (pin "1") (pinfunction "1_1") (pintype "input"))
      (node (ref "H4") (pin "1") (pinfunction "1_1") (pintype "input"))
      (node (ref "H4") (pin "18") (pinfunction "18_18") (pintype "input"))
      (node (ref "H5") (pin "4") (pinfunction "4_4") (pintype "unspecified"))
      (node (ref "R6") (pin "1") (pinfunction "1_1") (pintype "input"))
      (node (ref "R7") (pin "2") (pinfunction "2_2") (pintype "input"))
      (node (ref "U1") (pin "2") (pinfunction "VOUT_2") (pintype "unspecified"))
      (node (ref "U2") (pin "16") (pinfunction "VCC_16") (pintype "unspecified"))
      (node (ref "U2") (pin "4") (pinfunction "V3_4") (pintype "unspecified"))
      (node (ref "U6") (pin "24") (pinfunction "VDD_1_24") (pintype "unspecified"))
      (node (ref "U6") (pin "36") (pinfunction "VDD_2_36") (pintype "unspecified"))
      (node (ref "U6") (pin "48") (pinfunction "VDD_3_48") (pintype "unspecified"))
      (node (ref "U6") (pin "9") (pinfunction "VDDA_9") (pintype "unspecified"))
      (node (ref "U8") (pin "2") (pinfunction "A_2") (pintype "input"))
      (node (ref "U9") (pin "2") (pinfunction "A_2") (pintype "input"))
    )
    (net (code "52") (name "unconnected-(U2-CTS#-Pad9)") (class "Default")
      (node (ref "U2") (pin "9") (pinfunction "CTS#_9") (pintype "unspecified+no_connect"))
    )
    (net (code "53") (name "unconnected-(U2-DCD#-Pad12)") (class "Default")
      (node (ref "U2") (pin "12") (pinfunction "DCD#_12") (pintype "unspecified+no_connect"))
    )
    (net (code "54") (name "unconnected-(U2-DSR#-Pad10)") (class "Default")
      (node (ref "U2") (pin "10") (pinfunction "DSR#_10") (pintype "unspecified+no_connect"))
    )
    (net (code "55") (name "unconnected-(U2-DTR#-Pad13)") (class "Default")
      (node (ref "U2") (pin "13") (pinfunction "DTR#_13") (pintype "unspecified+no_connect"))
    )
    (net (code "56") (name "unconnected-(U2-NC.-Pad7)") (class "Default")
      (node (ref "U2") (pin "7") (pinfunction "NC._7") (pintype "unspecified+no_connect"))
    )
    (net (code "57") (name "unconnected-(U2-OUT#-Pad8)") (class "Default")
      (node (ref "U2") (pin "8") (pinfunction "OUT#_8") (pintype "unspecified+no_connect"))
    )
    (net (code "58") (name "unconnected-(U2-R232-Pad15)") (class "Default")
      (node (ref "U2") (pin "15") (pinfunction "R232_15") (pintype "unspecified+no_connect"))
    )
    (net (code "59") (name "unconnected-(U2-RI#-Pad11)") (class "Default")
      (node (ref "U2") (pin "11") (pinfunction "RI#_11") (pintype "unspecified+no_connect"))
    )
    (net (code "60") (name "unconnected-(U2-RTS#-Pad14)") (class "Default")
      (node (ref "U2") (pin "14") (pinfunction "RTS#_14") (pintype "unspecified+no_connect"))
    )
    (net (code "61") (name "unconnected-(U3-SH1-Pad6)") (class "Default")
      (node (ref "U3") (pin "6") (pinfunction "SH1_6") (pintype "unspecified+no_connect"))
    )
    (net (code "62") (name "unconnected-(U3-SH2-Pad7)") (class "Default")
      (node (ref "U3") (pin "7") (pinfunction "SH2_7") (pintype "unspecified+no_connect"))
    )
    (net (code "63") (name "unconnected-(U3-SH3-Pad8)") (class "Default")
      (node (ref "U3") (pin "8") (pinfunction "SH3_8") (pintype "unspecified+no_connect"))
    )
    (net (code "64") (name "unconnected-(U3-SH4-Pad9)") (class "Default")
      (node (ref "U3") (pin "9") (pinfunction "SH4_9") (pintype "unspecified+no_connect"))
    )
    (net (code "65") (name "unconnected-(U4-Pad3)") (class "Default")
      (node (ref "U4") (pin "3") (pinfunction "3_3") (pintype "unspecified+no_connect"))
    )
    (net (code "66") (name "unconnected-(U4-Pad6)") (class "Default")
      (node (ref "U4") (pin "6") (pinfunction "6_6") (pintype "unspecified+no_connect"))
    )
    (net (code "67") (name "unconnected-(U10-D-Pad5)") (class "Default")
      (node (ref "U10") (pin "5") (pinfunction "D_5") (pintype "unspecified"))
    )
    (net (code "68") (name "unconnected-(U10-E-Pad4)") (class "Default")
      (node (ref "U10") (pin "4") (pinfunction "E_4") (pintype "unspecified"))
    )
    (net (code "69") (name "unconnected-(U10-Pad6)") (class "Default")
      (node (ref "U10") (pin "6") (pinfunction "6_6") (pintype "unspecified+no_connect"))
    )
    (net (code "70") (name "unconnected-(U10-Pad7)") (class "Default")
      (node (ref "U10") (pin "7") (pinfunction "7_7") (pintype "unspecified+no_connect"))
    )
  )
)
